# ReSpeaker_Grove_Extension_Board_v1_0.net
KiCad netlist of a schematic drawn in EAGLE
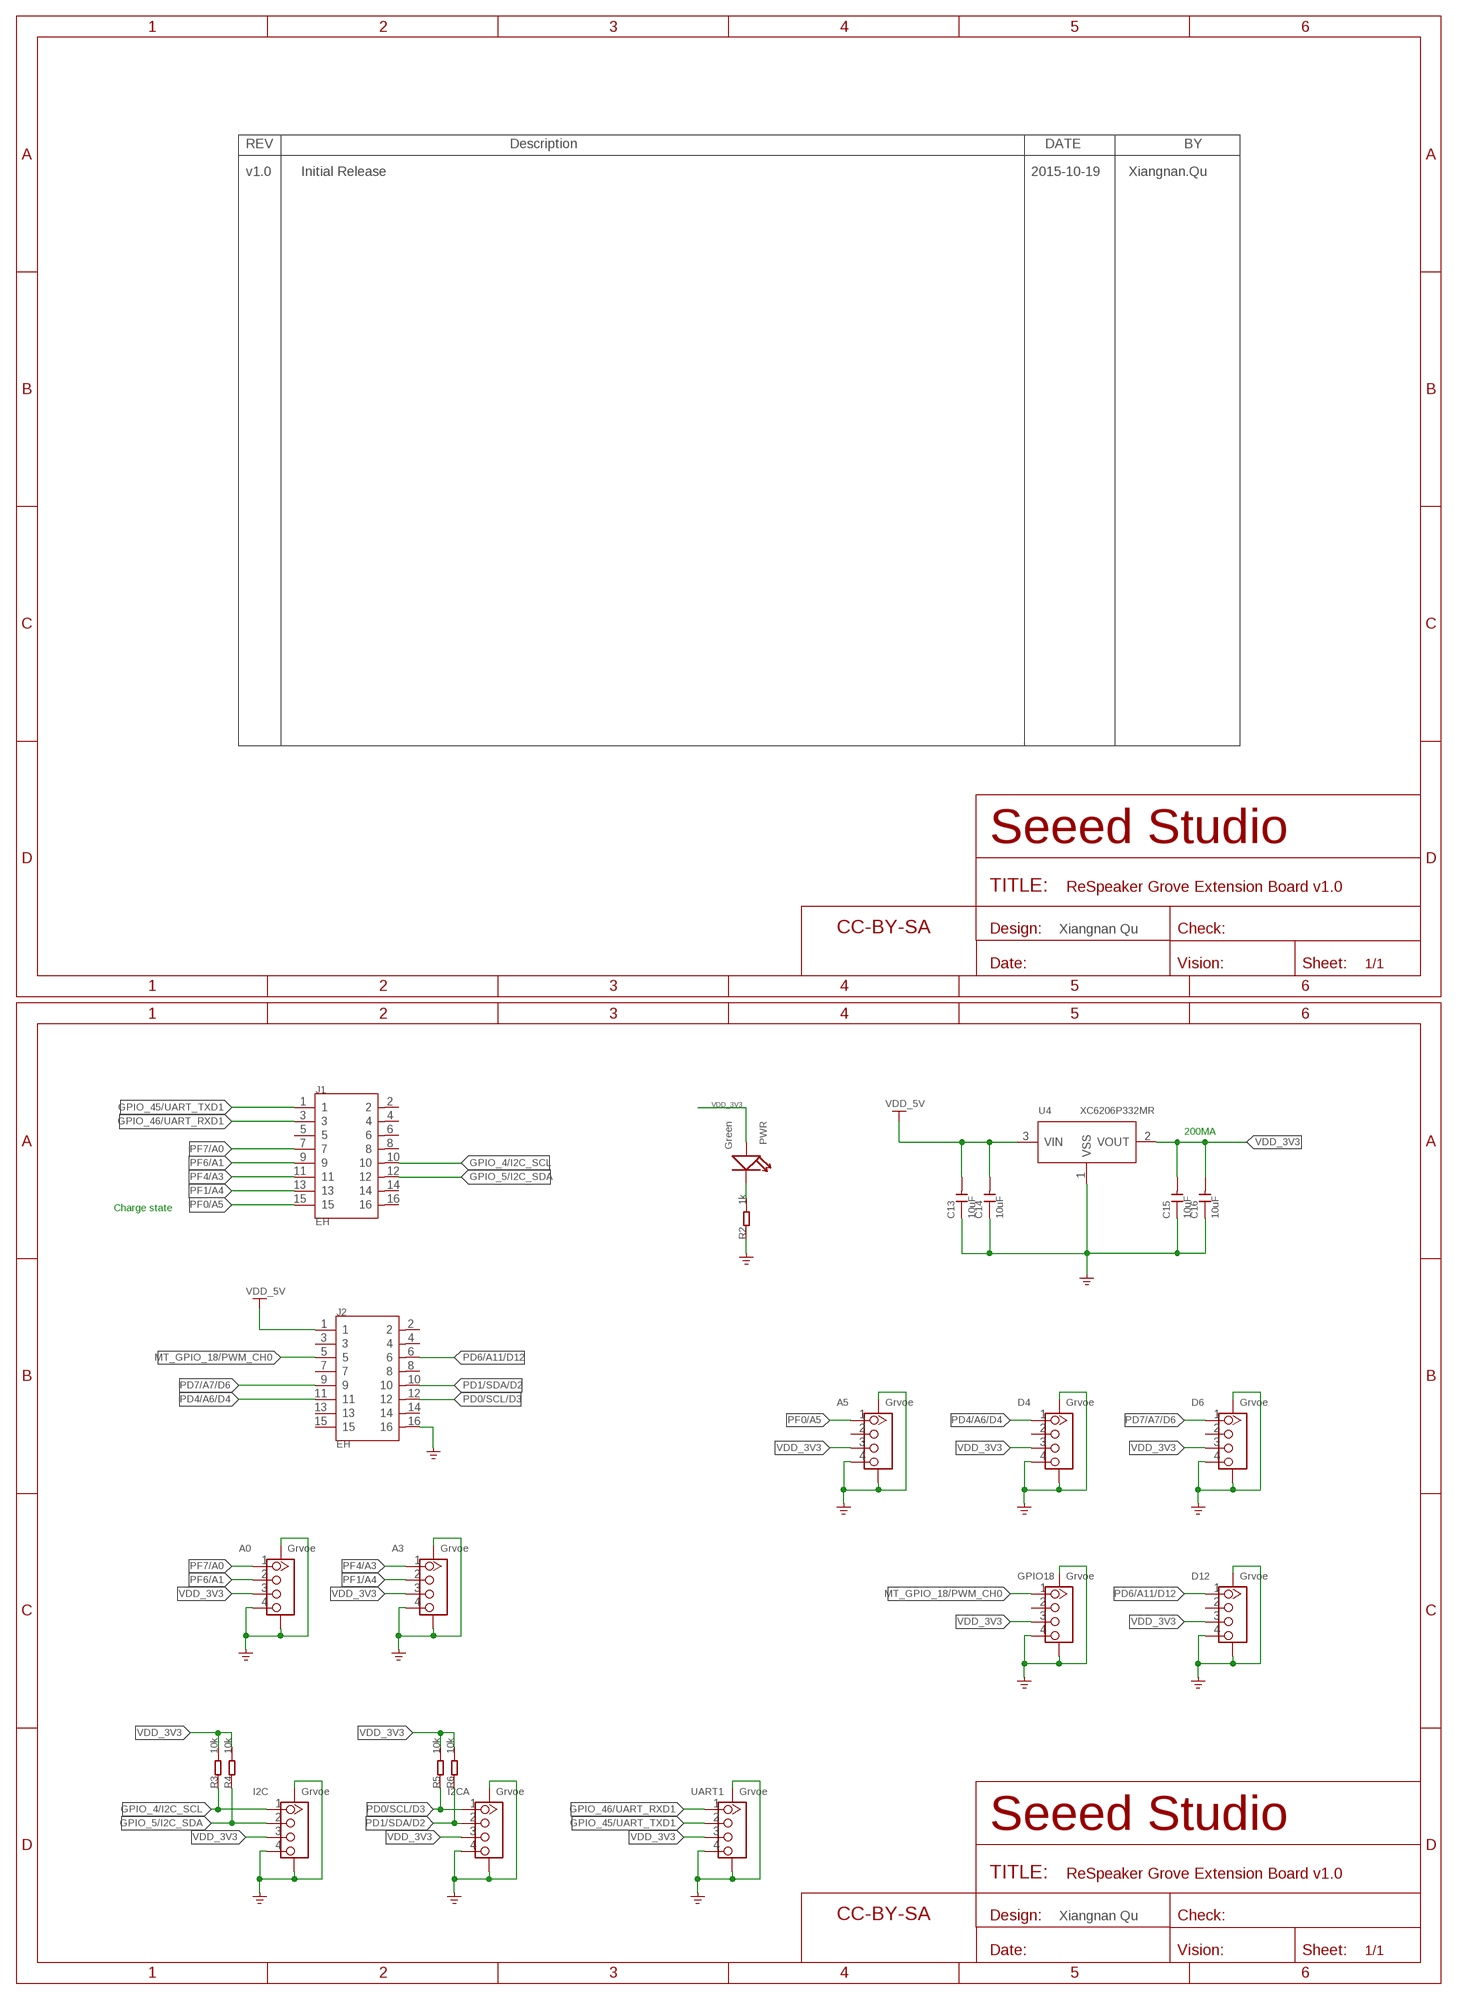
[diagram p0: schematic, sheet 1]

(export (version "E")
  (design (tool "Eeschema 10.0.6"))
  (components
    (comp (ref "A0")
      (value "Grvoe")
      (footprint "eagle-import:HW4-SMD-2.0-90D")
      (libsource (lib "eagle-import") (part "GROVE-CONNECTOR-SMD'90D'"))
    )
    (comp (ref "A3")
      (value "Grvoe")
      (footprint "eagle-import:HW4-SMD-2.0-90D")
      (libsource (lib "eagle-import") (part "GROVE-CONNECTOR-SMD'90D'"))
    )
    (comp (ref "A5")
      (value "Grvoe")
      (footprint "eagle-import:HW4-SMD-2.0-90D")
      (libsource (lib "eagle-import") (part "GROVE-CONNECTOR-SMD'90D'"))
    )
    (comp (ref "C13")
      (value "10uF")
      (footprint "eagle-import:C0603")
      (libsource (lib "eagle-import") (part "CAP-0603"))
    )
    (comp (ref "C14")
      (value "10uF")
      (footprint "eagle-import:C0603")
      (libsource (lib "eagle-import") (part "CAP-0603"))
    )
    (comp (ref "C15")
      (value "10uF")
      (footprint "eagle-import:C0603")
      (libsource (lib "eagle-import") (part "CAP-0603"))
    )
    (comp (ref "C16")
      (value "10uF")
      (footprint "eagle-import:C0603")
      (libsource (lib "eagle-import") (part "CAP-0603"))
    )
    (comp (ref "D4")
      (value "Grvoe")
      (footprint "eagle-import:HW4-SMD-2.0-90D")
      (libsource (lib "eagle-import") (part "GROVE-CONNECTOR-SMD'90D'"))
    )
    (comp (ref "D6")
      (value "Grvoe")
      (footprint "eagle-import:HW4-SMD-2.0-90D")
      (libsource (lib "eagle-import") (part "GROVE-CONNECTOR-SMD'90D'"))
    )
    (comp (ref "D12")
      (value "Grvoe")
      (footprint "eagle-import:HW4-SMD-2.0-90D")
      (libsource (lib "eagle-import") (part "GROVE-CONNECTOR-SMD'90D'"))
    )
    (comp (ref "FR1")
      (value "SEEEDSTUDIO-OPEN-SCH-FRAME")
      (footprint "eagle-import:SEEEDSTUDIO-PCB-FRAME")
      (libsource (lib "eagle-import") (part "SEEEDSTUDIO-OPEN-SCH-FRAME"))
    )
    (comp (ref "FR2")
      (value "SEEEDSTUDIO-OPEN-SCH-FRAME")
      (footprint "eagle-import:SEEEDSTUDIO-PCB-FRAME")
      (libsource (lib "eagle-import") (part "SEEEDSTUDIO-OPEN-SCH-FRAME"))
    )
    (comp (ref "GPIO18")
      (value "Grvoe")
      (footprint "eagle-import:HW4-SMD-2.0-90D")
      (libsource (lib "eagle-import") (part "GROVE-CONNECTOR-SMD'90D'"))
    )
    (comp (ref "I2C")
      (value "Grvoe")
      (footprint "eagle-import:HW4-SMD-2.0-90D")
      (libsource (lib "eagle-import") (part "GROVE-CONNECTOR-SMD'90D'"))
    )
    (comp (ref "I2CA")
      (value "Grvoe")
      (footprint "eagle-import:HW4-SMD-2.0-90D")
      (libsource (lib "eagle-import") (part "GROVE-CONNECTOR-SMD'90D'"))
    )
    (comp (ref "J1")
      (value "EH")
      (footprint "eagle-import:H2X8-2.0")
      (libsource (lib "eagle-import") (part "HEADER-2X8P2.0"))
    )
    (comp (ref "J2")
      (value "EH")
      (footprint "eagle-import:H2X8-2.0")
      (libsource (lib "eagle-import") (part "HEADER-2X8P2.0"))
    )
    (comp (ref "PWR")
      (value "Green")
      (footprint "eagle-import:LED-0402")
      (libsource (lib "eagle-import") (part "LED-0402"))
    )
    (comp (ref "R2")
      (value "1k")
      (footprint "eagle-import:R0402")
      (libsource (lib "eagle-import") (part "RES-0402"))
    )
    (comp (ref "R3")
      (value "10k")
      (footprint "eagle-import:R0402")
      (libsource (lib "eagle-import") (part "RES-0402"))
    )
    (comp (ref "R4")
      (value "10k")
      (footprint "eagle-import:R0402")
      (libsource (lib "eagle-import") (part "RES-0402"))
    )
    (comp (ref "R5")
      (value "10k")
      (footprint "eagle-import:R0402")
      (libsource (lib "eagle-import") (part "RES-0402"))
    )
    (comp (ref "R6")
      (value "10k")
      (footprint "eagle-import:R0402")
      (libsource (lib "eagle-import") (part "RES-0402"))
    )
    (comp (ref "U4")
      (value "XC6206P332MR")
      (footprint "eagle-import:SOT-23")
      (libsource (lib "eagle-import") (part "PMIC-XC6206PMR"))
    )
    (comp (ref "UART1")
      (value "Grvoe")
      (footprint "eagle-import:HW4-SMD-2.0-90D")
      (libsource (lib "eagle-import") (part "GROVE-CONNECTOR-SMD'90D'"))
    )
  )
  (nets
    (net (code "1") (name "GND_POWER") (class "Default")
      (node (ref "A0") (pin "4") (pinfunction "4_4") (pintype "bidirectional"))
      (node (ref "A0") (pin "SS1") (pinfunction "SS1_SS1") (pintype "bidirectional"))
      (node (ref "A0") (pin "SS2") (pinfunction "SS2_SS2") (pintype "bidirectional"))
      (node (ref "A3") (pin "4") (pinfunction "4_4") (pintype "bidirectional"))
      (node (ref "A3") (pin "SS1") (pinfunction "SS1_SS1") (pintype "bidirectional"))
      (node (ref "A3") (pin "SS2") (pinfunction "SS2_SS2") (pintype "bidirectional"))
      (node (ref "A5") (pin "4") (pinfunction "4_4") (pintype "bidirectional"))
      (node (ref "A5") (pin "SS1") (pinfunction "SS1_SS1") (pintype "bidirectional"))
      (node (ref "A5") (pin "SS2") (pinfunction "SS2_SS2") (pintype "bidirectional"))
      (node (ref "C13") (pin "1") (pinfunction "1_1") (pintype "passive"))
      (node (ref "C14") (pin "1") (pinfunction "1_1") (pintype "passive"))
      (node (ref "C15") (pin "1") (pinfunction "1_1") (pintype "passive"))
      (node (ref "C16") (pin "1") (pinfunction "1_1") (pintype "passive"))
      (node (ref "D12") (pin "4") (pinfunction "4_4") (pintype "bidirectional"))
      (node (ref "D12") (pin "SS1") (pinfunction "SS1_SS1") (pintype "bidirectional"))
      (node (ref "D12") (pin "SS2") (pinfunction "SS2_SS2") (pintype "bidirectional"))
      (node (ref "D4") (pin "4") (pinfunction "4_4") (pintype "bidirectional"))
      (node (ref "D4") (pin "SS1") (pinfunction "SS1_SS1") (pintype "bidirectional"))
      (node (ref "D4") (pin "SS2") (pinfunction "SS2_SS2") (pintype "bidirectional"))
      (node (ref "D6") (pin "4") (pinfunction "4_4") (pintype "bidirectional"))
      (node (ref "D6") (pin "SS1") (pinfunction "SS1_SS1") (pintype "bidirectional"))
      (node (ref "D6") (pin "SS2") (pinfunction "SS2_SS2") (pintype "bidirectional"))
      (node (ref "GPIO18") (pin "4") (pinfunction "4_4") (pintype "bidirectional"))
      (node (ref "GPIO18") (pin "SS1") (pinfunction "SS1_SS1") (pintype "bidirectional"))
      (node (ref "GPIO18") (pin "SS2") (pinfunction "SS2_SS2") (pintype "bidirectional"))
      (node (ref "I2C") (pin "4") (pinfunction "4_4") (pintype "bidirectional"))
      (node (ref "I2C") (pin "SS1") (pinfunction "SS1_SS1") (pintype "bidirectional"))
      (node (ref "I2C") (pin "SS2") (pinfunction "SS2_SS2") (pintype "bidirectional"))
      (node (ref "I2CA") (pin "4") (pinfunction "4_4") (pintype "bidirectional"))
      (node (ref "I2CA") (pin "SS1") (pinfunction "SS1_SS1") (pintype "bidirectional"))
      (node (ref "I2CA") (pin "SS2") (pinfunction "SS2_SS2") (pintype "bidirectional"))
      (node (ref "J2") (pin "16") (pinfunction "16_16") (pintype "bidirectional"))
      (node (ref "R2") (pin "1") (pinfunction "1_1") (pintype "passive"))
      (node (ref "U4") (pin "1") (pinfunction "VSS_1") (pintype "bidirectional"))
      (node (ref "UART1") (pin "4") (pinfunction "4_4") (pintype "bidirectional"))
      (node (ref "UART1") (pin "SS1") (pinfunction "SS1_SS1") (pintype "bidirectional"))
      (node (ref "UART1") (pin "SS2") (pinfunction "SS2_SS2") (pintype "bidirectional"))
    )
    (net (code "2") (name "GPIO_4{slash}I2C_SCL") (class "Default")
      (node (ref "I2C") (pin "1") (pinfunction "1_1") (pintype "bidirectional"))
      (node (ref "J1") (pin "10") (pinfunction "10_10") (pintype "bidirectional"))
      (node (ref "R3") (pin "1") (pinfunction "1_1") (pintype "passive"))
    )
    (net (code "3") (name "GPIO_5{slash}I2C_SDA") (class "Default")
      (node (ref "I2C") (pin "2") (pinfunction "2_2") (pintype "bidirectional"))
      (node (ref "J1") (pin "12") (pinfunction "12_12") (pintype "bidirectional"))
      (node (ref "R4") (pin "1") (pinfunction "1_1") (pintype "passive"))
    )
    (net (code "4") (name "GPIO_45{slash}UART_TXD1") (class "Default")
      (node (ref "J1") (pin "1") (pinfunction "1_1") (pintype "bidirectional"))
      (node (ref "UART1") (pin "2") (pinfunction "2_2") (pintype "bidirectional"))
    )
    (net (code "5") (name "GPIO_46{slash}UART_RXD1") (class "Default")
      (node (ref "J1") (pin "3") (pinfunction "3_3") (pintype "bidirectional"))
      (node (ref "UART1") (pin "1") (pinfunction "1_1") (pintype "bidirectional"))
    )
    (net (code "6") (name "MT_GPIO_18{slash}PWM_CH0") (class "Default")
      (node (ref "GPIO18") (pin "1") (pinfunction "1_1") (pintype "bidirectional"))
      (node (ref "J2") (pin "5") (pinfunction "5_5") (pintype "bidirectional"))
    )
    (net (code "7") (name "Net-(PWR-Pad-)") (class "Default")
      (node (ref "PWR") (pin "-") (pinfunction "-_-") (pintype "passive"))
      (node (ref "R2") (pin "2") (pinfunction "2_2") (pintype "passive"))
    )
    (net (code "8") (name "PD0{slash}SCL{slash}D3") (class "Default")
      (node (ref "I2CA") (pin "1") (pinfunction "1_1") (pintype "bidirectional"))
      (node (ref "J2") (pin "12") (pinfunction "12_12") (pintype "bidirectional"))
      (node (ref "R5") (pin "1") (pinfunction "1_1") (pintype "passive"))
    )
    (net (code "9") (name "PD1{slash}SDA{slash}D2") (class "Default")
      (node (ref "I2CA") (pin "2") (pinfunction "2_2") (pintype "bidirectional"))
      (node (ref "J2") (pin "10") (pinfunction "10_10") (pintype "bidirectional"))
      (node (ref "R6") (pin "1") (pinfunction "1_1") (pintype "passive"))
    )
    (net (code "10") (name "PD4{slash}A6{slash}D4") (class "Default")
      (node (ref "D4") (pin "1") (pinfunction "1_1") (pintype "bidirectional"))
      (node (ref "J2") (pin "11") (pinfunction "11_11") (pintype "bidirectional"))
    )
    (net (code "11") (name "PD6{slash}A11{slash}D12") (class "Default")
      (node (ref "D12") (pin "1") (pinfunction "1_1") (pintype "bidirectional"))
      (node (ref "J2") (pin "6") (pinfunction "6_6") (pintype "bidirectional"))
    )
    (net (code "12") (name "PD7{slash}A7{slash}D6") (class "Default")
      (node (ref "D6") (pin "1") (pinfunction "1_1") (pintype "bidirectional"))
      (node (ref "J2") (pin "9") (pinfunction "9_9") (pintype "bidirectional"))
    )
    (net (code "13") (name "PF0{slash}A5") (class "Default")
      (node (ref "A5") (pin "1") (pinfunction "1_1") (pintype "bidirectional"))
      (node (ref "J1") (pin "15") (pinfunction "15_15") (pintype "bidirectional"))
    )
    (net (code "14") (name "PF1{slash}A4") (class "Default")
      (node (ref "A3") (pin "2") (pinfunction "2_2") (pintype "bidirectional"))
      (node (ref "J1") (pin "13") (pinfunction "13_13") (pintype "bidirectional"))
    )
    (net (code "15") (name "PF4{slash}A3") (class "Default")
      (node (ref "A3") (pin "1") (pinfunction "1_1") (pintype "bidirectional"))
      (node (ref "J1") (pin "11") (pinfunction "11_11") (pintype "bidirectional"))
    )
    (net (code "16") (name "PF6{slash}A1") (class "Default")
      (node (ref "A0") (pin "2") (pinfunction "2_2") (pintype "bidirectional"))
      (node (ref "J1") (pin "9") (pinfunction "9_9") (pintype "bidirectional"))
    )
    (net (code "17") (name "PF7{slash}A0") (class "Default")
      (node (ref "A0") (pin "1") (pinfunction "1_1") (pintype "bidirectional"))
      (node (ref "J1") (pin "7") (pinfunction "7_7") (pintype "bidirectional"))
    )
    (net (code "18") (name "POWER_BAR") (class "Default")
      (node (ref "C13") (pin "2") (pinfunction "2_2") (pintype "passive"))
      (node (ref "C14") (pin "2") (pinfunction "2_2") (pintype "passive"))
      (node (ref "J2") (pin "1") (pinfunction "1_1") (pintype "bidirectional"))
      (node (ref "U4") (pin "3") (pinfunction "VIN_3") (pintype "bidirectional"))
    )
    (net (code "19") (name "VDD_3V3") (class "Default")
      (node (ref "A0") (pin "3") (pinfunction "3_3") (pintype "bidirectional"))
      (node (ref "A3") (pin "3") (pinfunction "3_3") (pintype "bidirectional"))
      (node (ref "A5") (pin "3") (pinfunction "3_3") (pintype "bidirectional"))
      (node (ref "C15") (pin "2") (pinfunction "2_2") (pintype "passive"))
      (node (ref "C16") (pin "2") (pinfunction "2_2") (pintype "passive"))
      (node (ref "D12") (pin "3") (pinfunction "3_3") (pintype "bidirectional"))
      (node (ref "D4") (pin "3") (pinfunction "3_3") (pintype "bidirectional"))
      (node (ref "D6") (pin "3") (pinfunction "3_3") (pintype "bidirectional"))
      (node (ref "GPIO18") (pin "3") (pinfunction "3_3") (pintype "bidirectional"))
      (node (ref "I2C") (pin "3") (pinfunction "3_3") (pintype "bidirectional"))
      (node (ref "I2CA") (pin "3") (pinfunction "3_3") (pintype "bidirectional"))
      (node (ref "PWR") (pin "+") (pinfunction "+_+") (pintype "passive"))
      (node (ref "R3") (pin "2") (pinfunction "2_2") (pintype "passive"))
      (node (ref "R4") (pin "2") (pinfunction "2_2") (pintype "passive"))
      (node (ref "R5") (pin "2") (pinfunction "2_2") (pintype "passive"))
      (node (ref "R6") (pin "2") (pinfunction "2_2") (pintype "passive"))
      (node (ref "U4") (pin "2") (pinfunction "VOUT_2") (pintype "bidirectional"))
      (node (ref "UART1") (pin "3") (pinfunction "3_3") (pintype "bidirectional"))
    )
    (net (code "20") (name "unconnected-(A5-Pad2)") (class "Default")
      (node (ref "A5") (pin "2") (pinfunction "2_2") (pintype "bidirectional"))
    )
    (net (code "21") (name "unconnected-(D4-Pad2)") (class "Default")
      (node (ref "D4") (pin "2") (pinfunction "2_2") (pintype "bidirectional"))
    )
    (net (code "22") (name "unconnected-(D6-Pad2)") (class "Default")
      (node (ref "D6") (pin "2") (pinfunction "2_2") (pintype "bidirectional"))
    )
    (net (code "23") (name "unconnected-(D12-Pad2)") (class "Default")
      (node (ref "D12") (pin "2") (pinfunction "2_2") (pintype "bidirectional"))
    )
    (net (code "24") (name "unconnected-(GPIO18-Pad2)") (class "Default")
      (node (ref "GPIO18") (pin "2") (pinfunction "2_2") (pintype "bidirectional"))
    )
    (net (code "25") (name "unconnected-(J1-Pad2)") (class "Default")
      (node (ref "J1") (pin "2") (pinfunction "2_2") (pintype "bidirectional"))
    )
    (net (code "26") (name "unconnected-(J1-Pad4)") (class "Default")
      (node (ref "J1") (pin "4") (pinfunction "4_4") (pintype "bidirectional"))
    )
    (net (code "27") (name "unconnected-(J1-Pad5)") (class "Default")
      (node (ref "J1") (pin "5") (pinfunction "5_5") (pintype "bidirectional"))
    )
    (net (code "28") (name "unconnected-(J1-Pad6)") (class "Default")
      (node (ref "J1") (pin "6") (pinfunction "6_6") (pintype "bidirectional"))
    )
    (net (code "29") (name "unconnected-(J1-Pad8)") (class "Default")
      (node (ref "J1") (pin "8") (pinfunction "8_8") (pintype "bidirectional"))
    )
    (net (code "30") (name "unconnected-(J1-Pad14)") (class "Default")
      (node (ref "J1") (pin "14") (pinfunction "14_14") (pintype "bidirectional"))
    )
    (net (code "31") (name "unconnected-(J1-Pad16)") (class "Default")
      (node (ref "J1") (pin "16") (pinfunction "16_16") (pintype "bidirectional"))
    )
    (net (code "32") (name "unconnected-(J2-Pad2)") (class "Default")
      (node (ref "J2") (pin "2") (pinfunction "2_2") (pintype "bidirectional"))
    )
    (net (code "33") (name "unconnected-(J2-Pad3)") (class "Default")
      (node (ref "J2") (pin "3") (pinfunction "3_3") (pintype "bidirectional"))
    )
    (net (code "34") (name "unconnected-(J2-Pad4)") (class "Default")
      (node (ref "J2") (pin "4") (pinfunction "4_4") (pintype "bidirectional"))
    )
    (net (code "35") (name "unconnected-(J2-Pad7)") (class "Default")
      (node (ref "J2") (pin "7") (pinfunction "7_7") (pintype "bidirectional"))
    )
    (net (code "36") (name "unconnected-(J2-Pad8)") (class "Default")
      (node (ref "J2") (pin "8") (pinfunction "8_8") (pintype "bidirectional"))
    )
    (net (code "37") (name "unconnected-(J2-Pad13)") (class "Default")
      (node (ref "J2") (pin "13") (pinfunction "13_13") (pintype "bidirectional"))
    )
    (net (code "38") (name "unconnected-(J2-Pad14)") (class "Default")
      (node (ref "J2") (pin "14") (pinfunction "14_14") (pintype "bidirectional"))
    )
    (net (code "39") (name "unconnected-(J2-Pad15)") (class "Default")
      (node (ref "J2") (pin "15") (pinfunction "15_15") (pintype "bidirectional"))
    )
  )
)
